# 09_Parallel_Camera.net
KiCad netlist of a schematic drawn in Altium Designer
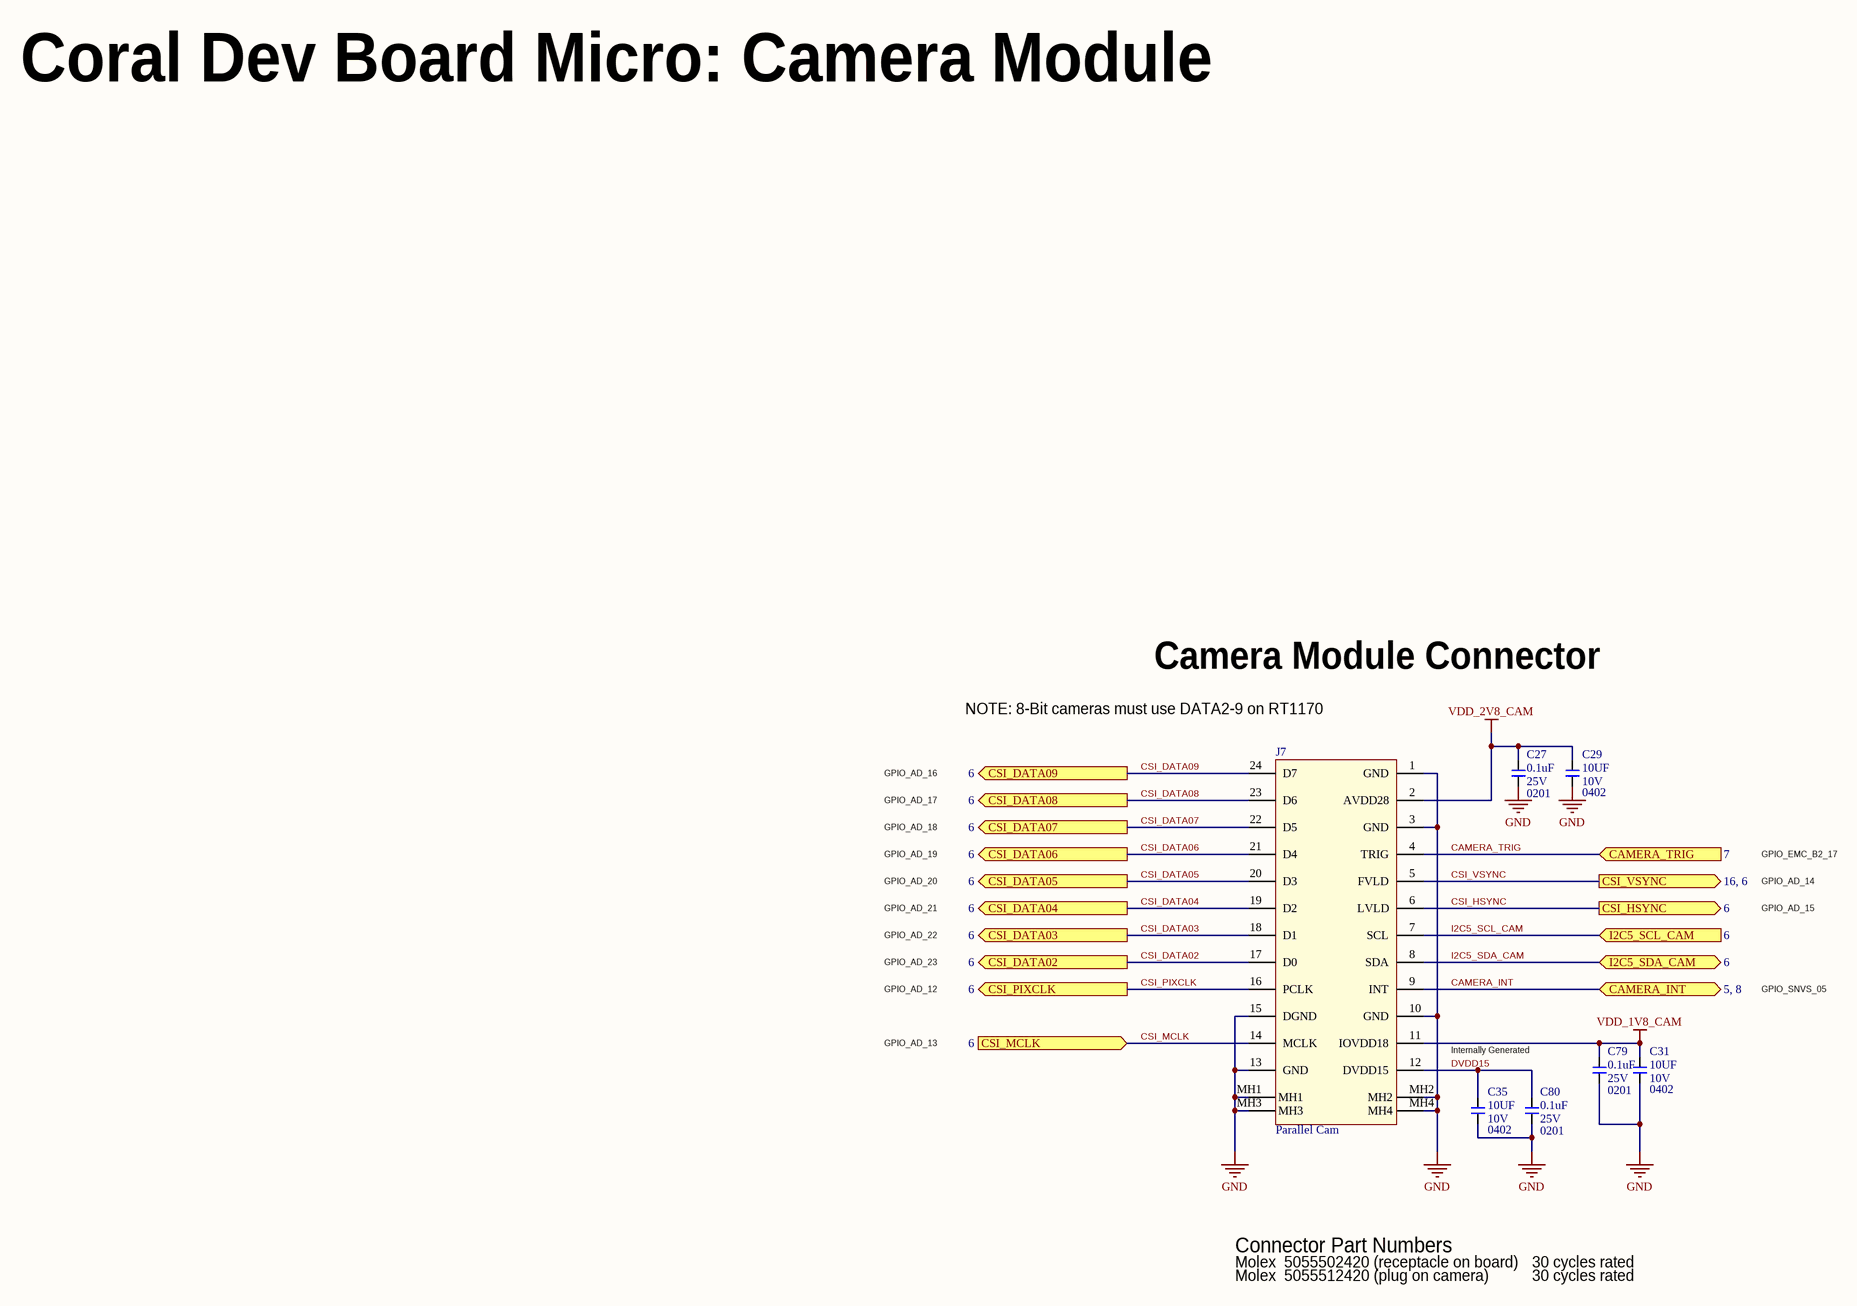
[diagram p0: 09 Parallel Camera.SchDoc]

(export (version "E")
  (design (tool "Eeschema 10.0.6"))
  (components
    (comp (ref "C27")
      (value "0.1uF")
      (footprint "C0201Y")
      (description "CAP, CER, X5R, 0.1uF, 25V, 20%, 0201, 0.33mm T")
      (fields
        (field (name "MFG") "MURATA")
        (field (name "PACKAGE") "0201")
        (field (name "VOLTAGE") "25V")
        (field (name "TOLERANCE") "20%")
      )
      (libsource (lib "AltiumReleaseLibDB") (part "__Template_Cap"))
    )
    (comp (ref "C29")
      (value "10UF")
      (footprint "C0402")
      (description "CAP, CER, X5R, 10uF, 10V, 20%, 0402, 0.7mm T")
      (fields
        (field (name "MFG") "SAMSUNG")
        (field (name "PACKAGE") "0402")
        (field (name "VOLTAGE") "10V")
        (field (name "TOLERANCE") "20%")
      )
      (libsource (lib "AltiumReleaseLibDB") (part "__Template_Cap"))
    )
    (comp (ref "C31")
      (value "10UF")
      (footprint "C0402")
      (description "CAP, CER, X5R, 10uF, 10V, 20%, 0402, 0.7mm T")
      (fields
        (field (name "MFG") "SAMSUNG")
        (field (name "PACKAGE") "0402")
        (field (name "VOLTAGE") "10V")
        (field (name "TOLERANCE") "20%")
      )
      (libsource (lib "AltiumReleaseLibDB") (part "__Template_Cap"))
    )
    (comp (ref "C35")
      (value "10UF")
      (footprint "C0402")
      (description "CAP, CER, X5R, 10uF, 10V, 20%, 0402, 0.7mm T")
      (fields
        (field (name "MFG") "SAMSUNG")
        (field (name "PACKAGE") "0402")
        (field (name "VOLTAGE") "10V")
        (field (name "TOLERANCE") "20%")
      )
      (libsource (lib "AltiumReleaseLibDB") (part "__Template_Cap"))
    )
    (comp (ref "C79")
      (value "0.1uF")
      (footprint "C0201Y")
      (description "CAP, CER, X5R, 0.1uF, 25V, 20%, 0201, 0.33mm T")
      (fields
        (field (name "MFG") "MURATA")
        (field (name "PACKAGE") "0201")
        (field (name "VOLTAGE") "25V")
        (field (name "TOLERANCE") "20%")
      )
      (libsource (lib "AltiumReleaseLibDB") (part "__Template_Cap"))
    )
    (comp (ref "C80")
      (value "0.1uF")
      (footprint "C0201Y")
      (description "CAP, CER, X5R, 0.1uF, 25V, 20%, 0201, 0.33mm T")
      (fields
        (field (name "MFG") "MURATA")
        (field (name "PACKAGE") "0201")
        (field (name "VOLTAGE") "25V")
        (field (name "TOLERANCE") "20%")
      )
      (libsource (lib "AltiumReleaseLibDB") (part "__Template_Cap"))
    )
    (comp (ref "J7")
      (value "1087")
      (footprint "Molex_5037722410_HM01B0")
      (description "HM01B0, CONN, RCPT, OUTER SHROUD, 2x12 PIN, 0.4MM P, 0.65MM H, GOLD, SM")
      (fields (field (name "MFG") "Molex") (field (name "MFG P/N") "Parallel Cam"))
      (libsource (lib "Valiant_P1") (part "1087"))
    )
  )
  (nets
    (net (code "1") (name "/CAMERA_INT") (class "Default")
      (node (ref "J7") (pin "9") (pinfunction "INT_9") (pintype "passive"))
    )
    (net (code "2") (name "/CAMERA_TRIG") (class "Default")
      (node (ref "J7") (pin "4") (pinfunction "TRIG_4") (pintype "passive"))
    )
    (net (code "3") (name "/CSI_DATA02") (class "Default")
      (node (ref "J7") (pin "17") (pinfunction "D0_17") (pintype "passive"))
    )
    (net (code "4") (name "/CSI_DATA03") (class "Default")
      (node (ref "J7") (pin "18") (pinfunction "D1_18") (pintype "passive"))
    )
    (net (code "5") (name "/CSI_DATA04") (class "Default")
      (node (ref "J7") (pin "19") (pinfunction "D2_19") (pintype "passive"))
    )
    (net (code "6") (name "/CSI_DATA05") (class "Default")
      (node (ref "J7") (pin "20") (pinfunction "D3_20") (pintype "passive"))
    )
    (net (code "7") (name "/CSI_DATA06") (class "Default")
      (node (ref "J7") (pin "21") (pinfunction "D4_21") (pintype "passive"))
    )
    (net (code "8") (name "/CSI_DATA07") (class "Default")
      (node (ref "J7") (pin "22") (pinfunction "D5_22") (pintype "passive"))
    )
    (net (code "9") (name "/CSI_DATA08") (class "Default")
      (node (ref "J7") (pin "23") (pinfunction "D6_23") (pintype "passive"))
    )
    (net (code "10") (name "/CSI_DATA09") (class "Default")
      (node (ref "J7") (pin "24") (pinfunction "D7_24") (pintype "passive"))
    )
    (net (code "11") (name "/CSI_HSYNC") (class "Default")
      (node (ref "J7") (pin "6") (pinfunction "LVLD_6") (pintype "passive"))
    )
    (net (code "12") (name "/CSI_MCLK") (class "Default")
      (node (ref "J7") (pin "14") (pinfunction "MCLK_14") (pintype "passive"))
    )
    (net (code "13") (name "/CSI_PIXCLK") (class "Default")
      (node (ref "J7") (pin "16") (pinfunction "PCLK_16") (pintype "passive"))
    )
    (net (code "14") (name "/CSI_VSYNC") (class "Default")
      (node (ref "J7") (pin "5") (pinfunction "FVLD_5") (pintype "passive"))
    )
    (net (code "15") (name "/DVDD15") (class "Default")
      (node (ref "C35") (pin "1") (pintype "passive"))
      (node (ref "C80") (pin "1") (pintype "passive"))
      (node (ref "J7") (pin "12") (pinfunction "DVDD15_12") (pintype "passive"))
    )
    (net (code "16") (name "/I2C5_SCL_CAM") (class "Default")
      (node (ref "J7") (pin "7") (pinfunction "SCL_7") (pintype "passive"))
    )
    (net (code "17") (name "/I2C5_SDA_CAM") (class "Default")
      (node (ref "J7") (pin "8") (pinfunction "SDA_8") (pintype "passive"))
    )
    (net (code "18") (name "GND") (class "Default")
      (node (ref "C27") (pin "2") (pintype "passive"))
      (node (ref "C29") (pin "2") (pintype "passive"))
      (node (ref "C31") (pin "2") (pintype "passive"))
      (node (ref "C35") (pin "2") (pintype "passive"))
      (node (ref "C79") (pin "2") (pintype "passive"))
      (node (ref "C80") (pin "2") (pintype "passive"))
      (node (ref "J7") (pin "1") (pinfunction "GND_1") (pintype "passive"))
      (node (ref "J7") (pin "10") (pinfunction "GND_10") (pintype "passive"))
      (node (ref "J7") (pin "13") (pinfunction "GND_13") (pintype "passive"))
      (node (ref "J7") (pin "15") (pinfunction "DGND_15") (pintype "passive"))
      (node (ref "J7") (pin "3") (pinfunction "GND_3") (pintype "passive"))
      (node (ref "J7") (pin "MH1") (pinfunction "MH1_MH1") (pintype "passive"))
      (node (ref "J7") (pin "MH2") (pinfunction "MH2_MH2") (pintype "passive"))
      (node (ref "J7") (pin "MH3") (pinfunction "MH3_MH3") (pintype "passive"))
      (node (ref "J7") (pin "MH4") (pinfunction "MH4_MH4") (pintype "passive"))
    )
    (net (code "19") (name "VDD_1V8_CAM") (class "Default")
      (node (ref "C31") (pin "1") (pintype "passive"))
      (node (ref "C79") (pin "1") (pintype "passive"))
      (node (ref "J7") (pin "11") (pinfunction "IOVDD18_11") (pintype "passive"))
    )
    (net (code "20") (name "VDD_2V8_CAM") (class "Default")
      (node (ref "C27") (pin "1") (pintype "passive"))
      (node (ref "C29") (pin "1") (pintype "passive"))
      (node (ref "J7") (pin "2") (pinfunction "AVDD28_2") (pintype "passive"))
    )
  )
)
